# 32sog.net
KiCad netlist of a schematic drawn in EAGLE
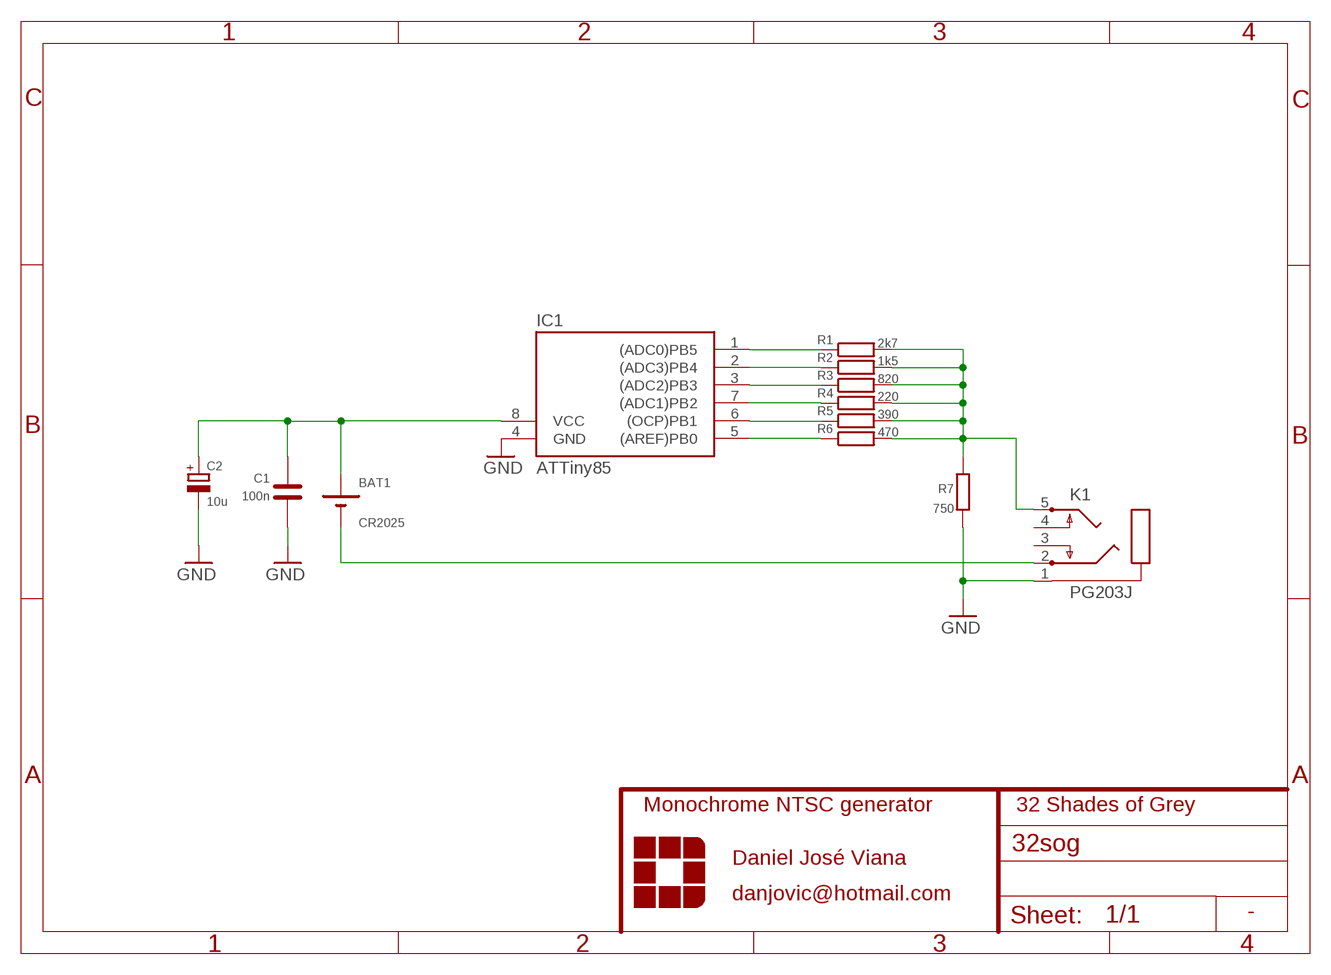
[diagram p0: schematic, sheet 1]

(export (version "E")
  (design (tool "Eeschema 10.0.6"))
  (components
    (comp (ref "BAT1")
      (value "CR2025")
      (footprint "eagle-import:CR2032-1GJ00245")
      (libsource (lib "eagle-import") (part "CR2032H1GJ00245"))
    )
    (comp (ref "C1")
      (value "100n")
      (footprint "eagle-import:C050-024X044")
      (libsource (lib "eagle-import") (part "CCERAMICO"))
    )
    (comp (ref "C2")
      (value "10u")
      (footprint "eagle-import:E2-4_LARGEPADS")
      (libsource (lib "eagle-import") (part "CPOL-EUE2-4_LARGEPADS"))
    )
    (comp (ref "IC1")
      (value "ATTiny85")
      (footprint "eagle-import:DIL08")
      (libsource (lib "eagle-import") (part "TINY15LP"))
    )
    (comp (ref "K1")
      (value "PG203J")
      (footprint "eagle-import:PG203J")
      (libsource (lib "eagle-import") (part "PG203J"))
    )
    (comp (ref "R1")
      (value "2k7")
      (footprint "eagle-import:0207_7")
      (libsource (lib "eagle-import") (part "R-EU_0207/7"))
    )
    (comp (ref "R2")
      (value "1k5")
      (footprint "eagle-import:0207_7")
      (libsource (lib "eagle-import") (part "R-EU_0207/7"))
    )
    (comp (ref "R3")
      (value "820")
      (footprint "eagle-import:0207_7")
      (libsource (lib "eagle-import") (part "R-EU_0207/7"))
    )
    (comp (ref "R4")
      (value "390")
      (footprint "eagle-import:0207_7")
      (libsource (lib "eagle-import") (part "R-EU_0207/7"))
    )
    (comp (ref "R5")
      (value "220")
      (footprint "eagle-import:0207_7")
      (libsource (lib "eagle-import") (part "R-EU_0207/7"))
    )
    (comp (ref "R6")
      (value "470")
      (footprint "eagle-import:0207_7")
      (libsource (lib "eagle-import") (part "R-EU_0207/7"))
    )
    (comp (ref "R7")
      (value "750")
      (footprint "eagle-import:0207_7")
      (libsource (lib "eagle-import") (part "R-EU_0207/7"))
    )
  )
  (nets
    (net (code "1") (name "GND") (class "Default")
      (node (ref "C1") (pin "1") (pinfunction "P$1_1") (pintype "bidirectional"))
      (node (ref "C2") (pin "-") (pinfunction "-_-") (pintype "passive"))
      (node (ref "IC1") (pin "4") (pinfunction "GND_4") (pintype "power_in"))
      (node (ref "K1") (pin "1") (pinfunction "1_1") (pintype "passive"))
      (node (ref "R7") (pin "2") (pinfunction "2_2") (pintype "passive"))
    )
    (net (code "2") (name "Net-(BAT1-PadMINUS)") (class "Default")
      (node (ref "BAT1") (pin "MINUS") (pinfunction "MINUS_MINUS") (pintype "passive"))
      (node (ref "K1") (pin "2") (pinfunction "2_2") (pintype "passive"))
    )
    (net (code "3") (name "Net-(C1-P$2)") (class "Default")
      (node (ref "BAT1") (pin "PLUS") (pinfunction "PLUS_PLUS") (pintype "passive"))
      (node (ref "C1") (pin "2") (pinfunction "P$2_2") (pintype "bidirectional"))
      (node (ref "C2") (pin "+") (pinfunction "+_+") (pintype "passive"))
      (node (ref "IC1") (pin "8") (pinfunction "VCC_8") (pintype "power_in"))
    )
    (net (code "4") (name "Net-(IC1-(ADC0)PB5)") (class "Default")
      (node (ref "IC1") (pin "1") (pinfunction "(ADC0)PB5_1") (pintype "bidirectional"))
      (node (ref "R1") (pin "1") (pinfunction "1_1") (pintype "passive"))
    )
    (net (code "5") (name "Net-(IC1-(ADC1)PB2)") (class "Default")
      (node (ref "IC1") (pin "7") (pinfunction "(ADC1)PB2_7") (pintype "bidirectional"))
      (node (ref "R4") (pin "1") (pinfunction "1_1") (pintype "passive"))
    )
    (net (code "6") (name "Net-(IC1-(ADC2)PB3)") (class "Default")
      (node (ref "IC1") (pin "3") (pinfunction "(ADC2)PB3_3") (pintype "bidirectional"))
      (node (ref "R3") (pin "1") (pinfunction "1_1") (pintype "passive"))
    )
    (net (code "7") (name "Net-(IC1-(ADC3)PB4)") (class "Default")
      (node (ref "IC1") (pin "2") (pinfunction "(ADC3)PB4_2") (pintype "bidirectional"))
      (node (ref "R2") (pin "1") (pinfunction "1_1") (pintype "passive"))
    )
    (net (code "8") (name "Net-(IC1-(AREF)PB0)") (class "Default")
      (node (ref "IC1") (pin "5") (pinfunction "(AREF)PB0_5") (pintype "bidirectional"))
      (node (ref "R6") (pin "1") (pinfunction "1_1") (pintype "passive"))
    )
    (net (code "9") (name "Net-(IC1-(OCP)PB1)") (class "Default")
      (node (ref "IC1") (pin "6") (pinfunction "(OCP)PB1_6") (pintype "bidirectional"))
      (node (ref "R5") (pin "1") (pinfunction "1_1") (pintype "passive"))
    )
    (net (code "10") (name "Net-(K1-Pad5)") (class "Default")
      (node (ref "K1") (pin "5") (pinfunction "5_5") (pintype "passive"))
      (node (ref "R1") (pin "2") (pinfunction "2_2") (pintype "passive"))
      (node (ref "R2") (pin "2") (pinfunction "2_2") (pintype "passive"))
      (node (ref "R3") (pin "2") (pinfunction "2_2") (pintype "passive"))
      (node (ref "R4") (pin "2") (pinfunction "2_2") (pintype "passive"))
      (node (ref "R5") (pin "2") (pinfunction "2_2") (pintype "passive"))
      (node (ref "R6") (pin "2") (pinfunction "2_2") (pintype "passive"))
      (node (ref "R7") (pin "1") (pinfunction "1_1") (pintype "passive"))
    )
    (net (code "11") (name "unconnected-(K1-Pad3)") (class "Default")
      (node (ref "K1") (pin "3") (pinfunction "3_3") (pintype "passive"))
    )
    (net (code "12") (name "unconnected-(K1-Pad4)") (class "Default")
      (node (ref "K1") (pin "4") (pinfunction "4_4") (pintype "passive"))
    )
  )
)
